# MCU.net
KiCad netlist of a schematic drawn in Altium Designer
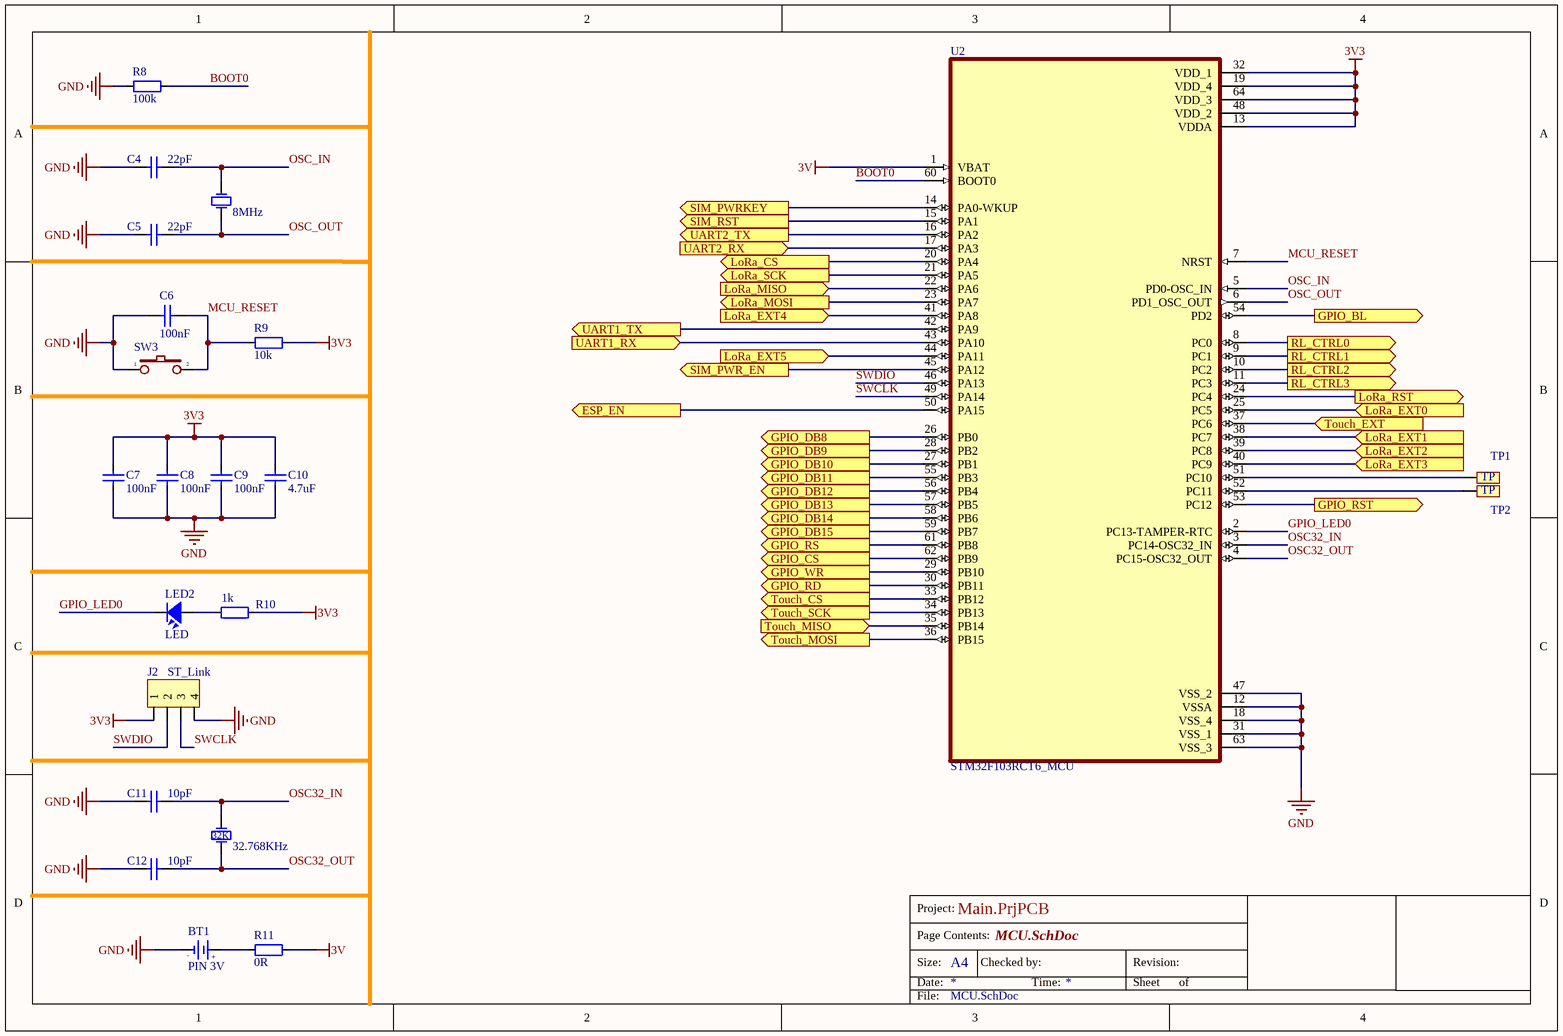
[diagram p0: MCU.SchDoc]

(export (version "E")
  (design (tool "Eeschema 10.0.6"))
  (components
    (comp (ref "BT1")
      (value "PIN 3V")
      (footprint "CR1220 SMD")
      (description "Battery 3VDC")
      (libsource (lib "My Library") (part "PIN 3V"))
    )
    (comp (ref "C4")
      (value "22pF")
      (footprint "CAP_0805")
      (description "Capacitor")
      (fields (field (name "PUBLISHER") "Altium Limited"))
      (libsource (lib "") (part "CapSMD_1"))
    )
    (comp (ref "C5")
      (value "22pF")
      (footprint "CAP_0805")
      (description "Capacitor")
      (fields (field (name "PUBLISHER") "Altium Limited"))
      (libsource (lib "") (part "CapSMD_1"))
    )
    (comp (ref "C6")
      (value "100nF")
      (footprint "CAP_0805")
      (description "Capacitor")
      (fields (field (name "PUBLISHER") "Altium Limited"))
      (libsource (lib "") (part "CapSMD_1"))
    )
    (comp (ref "C7")
      (value "100nF")
      (footprint "CAP_0805")
      (description "Capacitor")
      (fields (field (name "PUBLISHER") "Altium Limited"))
      (libsource (lib "My Library") (part "CapSMD"))
    )
    (comp (ref "C8")
      (value "100nF")
      (footprint "CAP_0805")
      (description "Capacitor")
      (fields (field (name "PUBLISHER") "Altium Limited"))
      (libsource (lib "My Library") (part "CapSMD"))
    )
    (comp (ref "C9")
      (value "100nF")
      (footprint "CAP_0805")
      (description "Capacitor")
      (fields (field (name "PUBLISHER") "Altium Limited"))
      (libsource (lib "My Library") (part "CapSMD"))
    )
    (comp (ref "C10")
      (value "4.7uF")
      (footprint "CAP_0805")
      (description "Capacitor")
      (fields (field (name "PUBLISHER") "Altium Limited"))
      (libsource (lib "My Library") (part "CapSMD"))
    )
    (comp (ref "C11")
      (value "10pF")
      (footprint "CAP_0805")
      (description "Capacitor")
      (fields (field (name "PUBLISHER") "Altium Limited"))
      (libsource (lib "") (part "CapSMD_1"))
    )
    (comp (ref "C12")
      (value "10pF")
      (footprint "CAP_0805")
      (description "Capacitor")
      (fields (field (name "PUBLISHER") "Altium Limited"))
      (libsource (lib "") (part "CapSMD_1"))
    )
    (comp (ref "J2")
      (value "ST_Link")
      (footprint "Header4 - SMD 1.25mm - B")
      (description "Header IDC, 4 x 1 Pin Vertical 2.54mm Pitch (Non-Boxed, Male)")
      (fields
        (field (name "MANUFACTURER") "Würth Elektronik eiSos GmbH")
        (field (name "PARTNO") "613002143121")
        (field (name "CREATED BY") "Karrer Zheng")
      )
      (libsource (lib "My Library") (part "Header4"))
    )
    (comp (ref "LED2")
      (value "LED")
      (footprint "LED-0805-Green")
      (description "LED Single colour Green and Red")
      (libsource (lib "My Library") (part "LED"))
    )
    (comp (ref "R8")
      (value "100k")
      (footprint "RES-SMD-0805")
      (description "Resistor")
      (fields
        (field (name "MANUFACTURER") "Generic Components")
        (field (name "PUBLISHER") "Altium Hobart Technology Centre")
      )
      (libsource (lib "My Library") (part "Resistor - SMD"))
    )
    (comp (ref "R9")
      (value "10k")
      (footprint "RES-SMD-0805")
      (description "Resistor")
      (fields
        (field (name "MANUFACTURER") "Generic Components")
        (field (name "PUBLISHER") "Altium Hobart Technology Centre")
      )
      (libsource (lib "My Library") (part "Resistor - SMD"))
    )
    (comp (ref "R10")
      (value "1k")
      (footprint "RES-SMD-0805")
      (description "Resistor")
      (fields
        (field (name "MANUFACTURER") "Generic Components")
        (field (name "PUBLISHER") "Altium Hobart Technology Centre")
      )
      (libsource (lib "My Library") (part "Resistor - SMD"))
    )
    (comp (ref "R11")
      (value "0R")
      (footprint "RES-SMD-0805")
      (description "Resistor")
      (fields
        (field (name "MANUFACTURER") "Generic Components")
        (field (name "PUBLISHER") "Altium Hobart Technology Centre")
      )
      (libsource (lib "My Library") (part "Resistor - SMD"))
    )
    (comp (ref "SW3")
      (value "SW")
      (footprint "SW 3x2x4")
      (description "Switch button 2 pin")
      (libsource (lib "My Library") (part "SW2"))
    )
    (comp (ref "TP1")
      (value "~")
      (footprint "TP_SMD")
      (description "CONNECT 1")
      (libsource (lib "My Library") (part "TP"))
    )
    (comp (ref "TP2")
      (value "~")
      (footprint "TP_SMD")
      (description "CONNECT 1")
      (libsource (lib "My Library") (part "TP"))
    )
    (comp (ref "U2")
      (value "STM32F103RCT6_MCU")
      (footprint "LQFP 64")
      (libsource (lib "My Library") (part "stm32f103rct6"))
    )
    (comp (ref "Y1")
      (value "8MHz")
      (footprint "XTAL")
      (description "Crystal Oscillator")
      (fields (field (name "PUBLISHER") "Altium Limited"))
      (libsource (lib "My Library") (part "XTAL"))
    )
    (comp (ref "Y2")
      (value "32.768KHz")
      (footprint "XTAL32K")
      (description "Crystal Oscillator")
      (fields (field (name "PUBLISHER") "Altium Limited"))
      (libsource (lib "My Library") (part "XTAL/32KHz"))
    )
  )
  (nets
    (net (code "1") (name "/BOOT0") (class "Default")
      (node (ref "R8") (pin "1") (pinfunction "1_1") (pintype "passive"))
      (node (ref "U2") (pin "60") (pinfunction "BOOT0_60") (pintype "input"))
    )
    (net (code "2") (name "/ESP_EN") (class "Default")
      (node (ref "U2") (pin "50") (pinfunction "PA15_50") (pintype "bidirectional"))
    )
    (net (code "3") (name "/GPIO_BL") (class "Default")
      (node (ref "U2") (pin "54") (pinfunction "PD2_54") (pintype "bidirectional"))
    )
    (net (code "4") (name "/GPIO_CS") (class "Default")
      (node (ref "U2") (pin "62") (pinfunction "PB9_62") (pintype "bidirectional"))
    )
    (net (code "5") (name "/GPIO_DB8") (class "Default")
      (node (ref "U2") (pin "26") (pinfunction "PB0_26") (pintype "bidirectional"))
    )
    (net (code "6") (name "/GPIO_DB9") (class "Default")
      (node (ref "U2") (pin "28") (pinfunction "PB2_28") (pintype "bidirectional"))
    )
    (net (code "7") (name "/GPIO_DB10") (class "Default")
      (node (ref "U2") (pin "27") (pinfunction "PB1_27") (pintype "bidirectional"))
    )
    (net (code "8") (name "/GPIO_DB11") (class "Default")
      (node (ref "U2") (pin "55") (pinfunction "PB3_55") (pintype "bidirectional"))
    )
    (net (code "9") (name "/GPIO_DB12") (class "Default")
      (node (ref "U2") (pin "56") (pinfunction "PB4_56") (pintype "bidirectional"))
    )
    (net (code "10") (name "/GPIO_DB13") (class "Default")
      (node (ref "U2") (pin "57") (pinfunction "PB5_57") (pintype "bidirectional"))
    )
    (net (code "11") (name "/GPIO_DB14") (class "Default")
      (node (ref "U2") (pin "58") (pinfunction "PB6_58") (pintype "bidirectional"))
    )
    (net (code "12") (name "/GPIO_DB15") (class "Default")
      (node (ref "U2") (pin "59") (pinfunction "PB7_59") (pintype "bidirectional"))
    )
    (net (code "13") (name "/GPIO_LED0") (class "Default")
      (node (ref "LED2") (pin "2") (pinfunction "2_2") (pintype "passive"))
      (node (ref "U2") (pin "2") (pinfunction "PC13-TAMPER-RTC_2") (pintype "bidirectional"))
    )
    (net (code "14") (name "/GPIO_RD") (class "Default")
      (node (ref "U2") (pin "30") (pinfunction "PB11_30") (pintype "bidirectional"))
    )
    (net (code "15") (name "/GPIO_RS") (class "Default")
      (node (ref "U2") (pin "61") (pinfunction "PB8_61") (pintype "bidirectional"))
    )
    (net (code "16") (name "/GPIO_RST") (class "Default")
      (node (ref "U2") (pin "53") (pinfunction "PC12_53") (pintype "bidirectional"))
    )
    (net (code "17") (name "/GPIO_WR") (class "Default")
      (node (ref "U2") (pin "29") (pinfunction "PB10_29") (pintype "bidirectional"))
    )
    (net (code "18") (name "/LoRa_CS") (class "Default")
      (node (ref "U2") (pin "20") (pinfunction "PA4_20") (pintype "bidirectional"))
    )
    (net (code "19") (name "/LoRa_EXT0") (class "Default")
      (node (ref "U2") (pin "25") (pinfunction "PC5_25") (pintype "bidirectional"))
    )
    (net (code "20") (name "/LoRa_EXT1") (class "Default")
      (node (ref "U2") (pin "38") (pinfunction "PC7_38") (pintype "bidirectional"))
    )
    (net (code "21") (name "/LoRa_EXT2") (class "Default")
      (node (ref "U2") (pin "39") (pinfunction "PC8_39") (pintype "bidirectional"))
    )
    (net (code "22") (name "/LoRa_EXT3") (class "Default")
      (node (ref "U2") (pin "40") (pinfunction "PC9_40") (pintype "bidirectional"))
    )
    (net (code "23") (name "/LoRa_EXT4") (class "Default")
      (node (ref "U2") (pin "41") (pinfunction "PA8_41") (pintype "bidirectional"))
    )
    (net (code "24") (name "/LoRa_EXT5") (class "Default")
      (node (ref "U2") (pin "44") (pinfunction "PA11_44") (pintype "bidirectional"))
    )
    (net (code "25") (name "/LoRa_MISO") (class "Default")
      (node (ref "U2") (pin "22") (pinfunction "PA6_22") (pintype "bidirectional"))
    )
    (net (code "26") (name "/LoRa_MOSI") (class "Default")
      (node (ref "U2") (pin "23") (pinfunction "PA7_23") (pintype "bidirectional"))
    )
    (net (code "27") (name "/LoRa_RST") (class "Default")
      (node (ref "U2") (pin "24") (pinfunction "PC4_24") (pintype "bidirectional"))
    )
    (net (code "28") (name "/LoRa_SCK") (class "Default")
      (node (ref "U2") (pin "21") (pinfunction "PA5_21") (pintype "bidirectional"))
    )
    (net (code "29") (name "/MCU_RESET") (class "Default")
      (node (ref "C6") (pin "2") (pinfunction "2_2") (pintype "passive"))
      (node (ref "R9") (pin "2") (pinfunction "2_2") (pintype "passive"))
      (node (ref "SW3") (pin "2") (pinfunction "2_2") (pintype "passive"))
      (node (ref "U2") (pin "7") (pinfunction "NRST_7") (pintype "input"))
    )
    (net (code "30") (name "/OSC32_IN") (class "Default")
      (node (ref "C11") (pin "2") (pinfunction "2_2") (pintype "passive"))
      (node (ref "U2") (pin "3") (pinfunction "PC14-OSC32_IN_3") (pintype "bidirectional"))
      (node (ref "Y2") (pin "1") (pinfunction "OSC1_1") (pintype "passive"))
    )
    (net (code "31") (name "/OSC32_OUT") (class "Default")
      (node (ref "C12") (pin "2") (pinfunction "2_2") (pintype "passive"))
      (node (ref "U2") (pin "4") (pinfunction "PC15-OSC32_OUT_4") (pintype "bidirectional"))
      (node (ref "Y2") (pin "2") (pinfunction "OSC2_2") (pintype "passive"))
    )
    (net (code "32") (name "/OSC_IN") (class "Default")
      (node (ref "C4") (pin "2") (pinfunction "2_2") (pintype "passive"))
      (node (ref "U2") (pin "5") (pinfunction "PD0-OSC_IN_5") (pintype "input"))
      (node (ref "Y1") (pin "1") (pinfunction "OSC1_1") (pintype "passive"))
    )
    (net (code "33") (name "/OSC_OUT") (class "Default")
      (node (ref "C5") (pin "2") (pinfunction "2_2") (pintype "passive"))
      (node (ref "U2") (pin "6") (pinfunction "PD1_OSC_OUT_6") (pintype "output"))
      (node (ref "Y1") (pin "2") (pinfunction "OSC2_2") (pintype "passive"))
    )
    (net (code "34") (name "/RL_CTRL0") (class "Default")
      (node (ref "U2") (pin "8") (pinfunction "PC0_8") (pintype "bidirectional"))
    )
    (net (code "35") (name "/RL_CTRL1") (class "Default")
      (node (ref "U2") (pin "9") (pinfunction "PC1_9") (pintype "bidirectional"))
    )
    (net (code "36") (name "/RL_CTRL2") (class "Default")
      (node (ref "U2") (pin "10") (pinfunction "PC2_10") (pintype "bidirectional"))
    )
    (net (code "37") (name "/RL_CTRL3") (class "Default")
      (node (ref "U2") (pin "11") (pinfunction "PC3_11") (pintype "bidirectional"))
    )
    (net (code "38") (name "/SIM_PWRKEY") (class "Default")
      (node (ref "U2") (pin "14") (pinfunction "PA0-WKUP_14") (pintype "bidirectional"))
    )
    (net (code "39") (name "/SIM_PWR_EN") (class "Default")
      (node (ref "U2") (pin "45") (pinfunction "PA12_45") (pintype "bidirectional"))
    )
    (net (code "40") (name "/SIM_RST") (class "Default")
      (node (ref "U2") (pin "15") (pinfunction "PA1_15") (pintype "bidirectional"))
    )
    (net (code "41") (name "/SWCLK") (class "Default")
      (node (ref "J2") (pin "3") (pinfunction "3_3") (pintype "passive"))
      (node (ref "U2") (pin "49") (pinfunction "PA14_49") (pintype "bidirectional"))
    )
    (net (code "42") (name "/SWDIO") (class "Default")
      (node (ref "J2") (pin "2") (pinfunction "2_2") (pintype "passive"))
      (node (ref "U2") (pin "46") (pinfunction "PA13_46") (pintype "bidirectional"))
    )
    (net (code "43") (name "/Touch_CS") (class "Default")
      (node (ref "U2") (pin "33") (pinfunction "PB12_33") (pintype "bidirectional"))
    )
    (net (code "44") (name "/Touch_EXT") (class "Default")
      (node (ref "U2") (pin "37") (pinfunction "PC6_37") (pintype "bidirectional"))
    )
    (net (code "45") (name "/Touch_MISO") (class "Default")
      (node (ref "U2") (pin "35") (pinfunction "PB14_35") (pintype "bidirectional"))
    )
    (net (code "46") (name "/Touch_MOSI") (class "Default")
      (node (ref "U2") (pin "36") (pinfunction "PB15_36") (pintype "bidirectional"))
    )
    (net (code "47") (name "/Touch_SCK") (class "Default")
      (node (ref "U2") (pin "34") (pinfunction "PB13_34") (pintype "bidirectional"))
    )
    (net (code "48") (name "/UART1_RX") (class "Default")
      (node (ref "U2") (pin "43") (pinfunction "PA10_43") (pintype "bidirectional"))
    )
    (net (code "49") (name "/UART1_TX") (class "Default")
      (node (ref "U2") (pin "42") (pinfunction "PA9_42") (pintype "bidirectional"))
    )
    (net (code "50") (name "/UART2_RX") (class "Default")
      (node (ref "U2") (pin "17") (pinfunction "PA3_17") (pintype "bidirectional"))
    )
    (net (code "51") (name "/UART2_TX") (class "Default")
      (node (ref "U2") (pin "16") (pinfunction "PA2_16") (pintype "bidirectional"))
    )
    (net (code "52") (name "3V") (class "Default")
      (node (ref "R11") (pin "1") (pinfunction "1_1") (pintype "passive"))
      (node (ref "U2") (pin "1") (pinfunction "VBAT_1") (pintype "input"))
    )
    (net (code "53") (name "3V3") (class "Default")
      (node (ref "C10") (pin "2") (pinfunction "2_2") (pintype "passive"))
      (node (ref "C7") (pin "2") (pinfunction "2_2") (pintype "passive"))
      (node (ref "C8") (pin "2") (pinfunction "2_2") (pintype "passive"))
      (node (ref "C9") (pin "2") (pinfunction "2_2") (pintype "passive"))
      (node (ref "J2") (pin "1") (pinfunction "1_1") (pintype "passive"))
      (node (ref "R10") (pin "1") (pinfunction "1_1") (pintype "passive"))
      (node (ref "R9") (pin "1") (pinfunction "1_1") (pintype "passive"))
      (node (ref "U2") (pin "13") (pinfunction "VDDA_13") (pintype "power_in"))
      (node (ref "U2") (pin "19") (pinfunction "VDD_4_19") (pintype "power_in"))
      (node (ref "U2") (pin "32") (pinfunction "VDD_1_32") (pintype "power_in"))
      (node (ref "U2") (pin "48") (pinfunction "VDD_2_48") (pintype "power_in"))
      (node (ref "U2") (pin "64") (pinfunction "VDD_3_64") (pintype "power_in"))
    )
    (net (code "54") (name "GND") (class "Default")
      (node (ref "BT1") (pin "2") (pinfunction "GND_2") (pintype "passive"))
      (node (ref "C10") (pin "1") (pinfunction "1_1") (pintype "passive"))
      (node (ref "C11") (pin "1") (pinfunction "1_1") (pintype "passive"))
      (node (ref "C12") (pin "1") (pinfunction "1_1") (pintype "passive"))
      (node (ref "C4") (pin "1") (pinfunction "1_1") (pintype "passive"))
      (node (ref "C5") (pin "1") (pinfunction "1_1") (pintype "passive"))
      (node (ref "C6") (pin "1") (pinfunction "1_1") (pintype "passive"))
      (node (ref "C7") (pin "1") (pinfunction "1_1") (pintype "passive"))
      (node (ref "C8") (pin "1") (pinfunction "1_1") (pintype "passive"))
      (node (ref "C9") (pin "1") (pinfunction "1_1") (pintype "passive"))
      (node (ref "J2") (pin "4") (pinfunction "4_4") (pintype "passive"))
      (node (ref "R8") (pin "2") (pinfunction "2_2") (pintype "passive"))
      (node (ref "SW3") (pin "1") (pinfunction "1_1") (pintype "passive"))
      (node (ref "U2") (pin "12") (pinfunction "VSSA_12") (pintype "power_in"))
      (node (ref "U2") (pin "18") (pinfunction "VSS_4_18") (pintype "power_in"))
      (node (ref "U2") (pin "31") (pinfunction "VSS_1_31") (pintype "power_in"))
      (node (ref "U2") (pin "47") (pinfunction "VSS_2_47") (pintype "power_in"))
      (node (ref "U2") (pin "63") (pinfunction "VSS_3_63") (pintype "power_in"))
    )
    (net (code "55") (name "Net-(BT1-+3V)") (class "Default")
      (node (ref "BT1") (pin "1") (pinfunction "+3V_1") (pintype "passive"))
      (node (ref "R11") (pin "2") (pinfunction "2_2") (pintype "passive"))
    )
    (net (code "56") (name "Net-(LED2-Pad1)") (class "Default")
      (node (ref "LED2") (pin "1") (pinfunction "1_1") (pintype "passive"))
      (node (ref "R10") (pin "2") (pinfunction "2_2") (pintype "passive"))
    )
    (net (code "57") (name "Net-(TP1-0)") (class "Default")
      (node (ref "TP1") (pin "1") (pinfunction "0_1") (pintype "passive"))
      (node (ref "U2") (pin "51") (pinfunction "PC10_51") (pintype "bidirectional"))
    )
    (net (code "58") (name "Net-(TP2-0)") (class "Default")
      (node (ref "TP2") (pin "1") (pinfunction "0_1") (pintype "passive"))
      (node (ref "U2") (pin "52") (pinfunction "PC11_52") (pintype "bidirectional"))
    )
  )
)
